# MIDI_Roundabout_revA.net
KiCad netlist of a schematic drawn in EAGLE
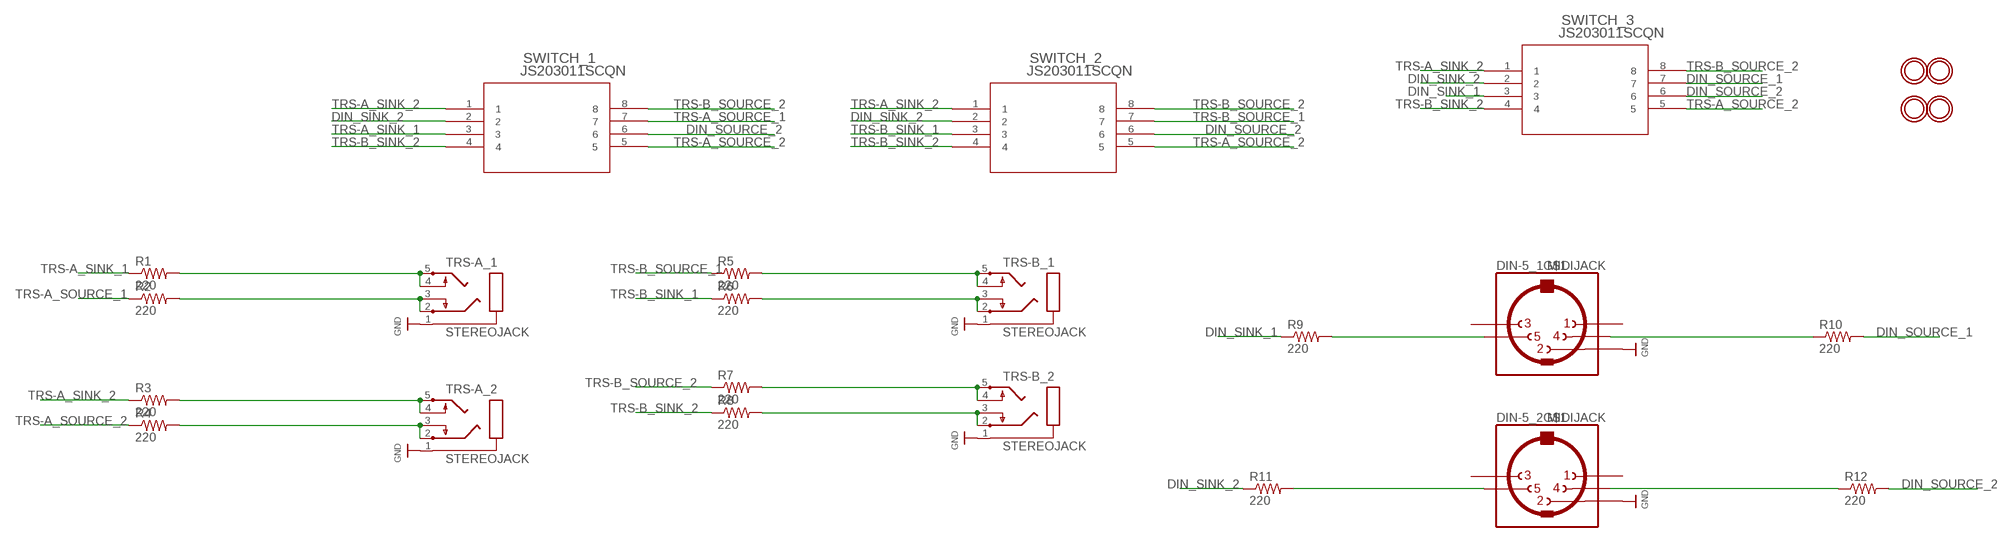
[diagram p0: schematic, sheet 1]

(export (version "E")
  (design (tool "Eeschema 10.0.6"))
  (components
    (comp (ref "DIN-5_1")
      (value "MIDIJACK")
      (footprint "eagle-import:CP-2350")
      (libsource (lib "eagle-import") (part "MIDIJACK"))
    )
    (comp (ref "DIN-5_2")
      (value "MIDIJACK")
      (footprint "eagle-import:CP-2350")
      (libsource (lib "eagle-import") (part "MIDIJACK"))
    )
    (comp (ref "R1")
      (value "220")
      (footprint "eagle-import:R0805")
      (libsource (lib "eagle-import") (part "R-US_R0805"))
    )
    (comp (ref "R2")
      (value "220")
      (footprint "eagle-import:R0805")
      (libsource (lib "eagle-import") (part "R-US_R0805"))
    )
    (comp (ref "R3")
      (value "220")
      (footprint "eagle-import:R0805")
      (libsource (lib "eagle-import") (part "R-US_R0805"))
    )
    (comp (ref "R4")
      (value "220")
      (footprint "eagle-import:R0805")
      (libsource (lib "eagle-import") (part "R-US_R0805"))
    )
    (comp (ref "R5")
      (value "220")
      (footprint "eagle-import:R0805")
      (libsource (lib "eagle-import") (part "R-US_R0805"))
    )
    (comp (ref "R6")
      (value "220")
      (footprint "eagle-import:R0805")
      (libsource (lib "eagle-import") (part "R-US_R0805"))
    )
    (comp (ref "R7")
      (value "220")
      (footprint "eagle-import:R0805")
      (libsource (lib "eagle-import") (part "R-US_R0805"))
    )
    (comp (ref "R8")
      (value "220")
      (footprint "eagle-import:R0805")
      (libsource (lib "eagle-import") (part "R-US_R0805"))
    )
    (comp (ref "R9")
      (value "220")
      (footprint "eagle-import:R0805")
      (libsource (lib "eagle-import") (part "R-US_R0805"))
    )
    (comp (ref "R10")
      (value "220")
      (footprint "eagle-import:R0805")
      (libsource (lib "eagle-import") (part "R-US_R0805"))
    )
    (comp (ref "R11")
      (value "220")
      (footprint "eagle-import:R0805")
      (libsource (lib "eagle-import") (part "R-US_R0805"))
    )
    (comp (ref "R12")
      (value "220")
      (footprint "eagle-import:R0805")
      (libsource (lib "eagle-import") (part "R-US_R0805"))
    )
    (comp (ref "SWITCH_1")
      (value "JS203011SCQN")
      (footprint "eagle-import:SWITCH_3011SCQN")
      (fields (field (name "COPYRIGHT") "Copyright (C) 2025 Ultra Librarian. All rights reserved."))
      (libsource (lib "eagle-import") (part "JS203011SCQN"))
    )
    (comp (ref "SWITCH_2")
      (value "JS203011SCQN")
      (footprint "eagle-import:SWITCH_3011SCQN")
      (fields (field (name "COPYRIGHT") "Copyright (C) 2025 Ultra Librarian. All rights reserved."))
      (libsource (lib "eagle-import") (part "JS203011SCQN"))
    )
    (comp (ref "SWITCH_3")
      (value "JS203011SCQN")
      (footprint "eagle-import:SWITCH_3011SCQN")
      (fields (field (name "COPYRIGHT") "Copyright (C) 2025 Ultra Librarian. All rights reserved."))
      (libsource (lib "eagle-import") (part "JS203011SCQN"))
    )
    (comp (ref "TRS-A_1")
      (value "STEREOJACK")
      (footprint "eagle-import:STX3100")
      (libsource (lib "eagle-import") (part "STEREOJACK"))
    )
    (comp (ref "TRS-A_2")
      (value "STEREOJACK")
      (footprint "eagle-import:STX3100")
      (libsource (lib "eagle-import") (part "STEREOJACK"))
    )
    (comp (ref "TRS-B_1")
      (value "STEREOJACK")
      (footprint "eagle-import:STX3100")
      (libsource (lib "eagle-import") (part "STEREOJACK"))
    )
    (comp (ref "TRS-B_2")
      (value "STEREOJACK")
      (footprint "eagle-import:STX3100")
      (libsource (lib "eagle-import") (part "STEREOJACK"))
    )
    (comp (ref "U$7")
      (value "MOUNTINGHOLE2.5_THICK")
      (footprint "eagle-import:MOUNTINGHOLE_2.5_PLATED_THICK")
      (libsource (lib "eagle-import") (part "MOUNTINGHOLE2.5_THICK"))
    )
    (comp (ref "U$8")
      (value "MOUNTINGHOLE2.5_THICK")
      (footprint "eagle-import:MOUNTINGHOLE_2.5_PLATED_THICK")
      (libsource (lib "eagle-import") (part "MOUNTINGHOLE2.5_THICK"))
    )
    (comp (ref "U$9")
      (value "MOUNTINGHOLE2.5_THICK")
      (footprint "eagle-import:MOUNTINGHOLE_2.5_PLATED_THICK")
      (libsource (lib "eagle-import") (part "MOUNTINGHOLE2.5_THICK"))
    )
    (comp (ref "U$10")
      (value "MOUNTINGHOLE2.5_THICK")
      (footprint "eagle-import:MOUNTINGHOLE_2.5_PLATED_THICK")
      (libsource (lib "eagle-import") (part "MOUNTINGHOLE2.5_THICK"))
    )
  )
  (nets
    (net (code "1") (name "/DIN_SINK_1") (class "Default")
      (node (ref "R9") (pin "1") (pinfunction "1_1") (pintype "passive"))
      (node (ref "SWITCH_3") (pin "3") (pinfunction "3_3") (pintype "passive"))
    )
    (net (code "2") (name "/DIN_SINK_2") (class "Default")
      (node (ref "R11") (pin "1") (pinfunction "1_1") (pintype "passive"))
      (node (ref "SWITCH_1") (pin "2") (pinfunction "2_2") (pintype "passive"))
      (node (ref "SWITCH_2") (pin "2") (pinfunction "2_2") (pintype "passive"))
      (node (ref "SWITCH_3") (pin "2") (pinfunction "2_2") (pintype "passive"))
    )
    (net (code "3") (name "/DIN_SOURCE_1") (class "Default")
      (node (ref "R10") (pin "2") (pinfunction "2_2") (pintype "passive"))
      (node (ref "SWITCH_3") (pin "7") (pinfunction "7_7") (pintype "passive"))
    )
    (net (code "4") (name "/DIN_SOURCE_2") (class "Default")
      (node (ref "R12") (pin "2") (pinfunction "2_2") (pintype "passive"))
      (node (ref "SWITCH_1") (pin "6") (pinfunction "6_6") (pintype "passive"))
      (node (ref "SWITCH_2") (pin "6") (pinfunction "6_6") (pintype "passive"))
      (node (ref "SWITCH_3") (pin "6") (pinfunction "6_6") (pintype "passive"))
    )
    (net (code "5") (name "/TRS-A_SINK_1") (class "Default")
      (node (ref "R1") (pin "1") (pinfunction "1_1") (pintype "passive"))
      (node (ref "SWITCH_1") (pin "3") (pinfunction "3_3") (pintype "passive"))
    )
    (net (code "6") (name "/TRS-A_SINK_2") (class "Default")
      (node (ref "R3") (pin "1") (pinfunction "1_1") (pintype "passive"))
      (node (ref "SWITCH_1") (pin "1") (pinfunction "1_1") (pintype "passive"))
      (node (ref "SWITCH_2") (pin "1") (pinfunction "1_1") (pintype "passive"))
      (node (ref "SWITCH_3") (pin "1") (pinfunction "1_1") (pintype "passive"))
    )
    (net (code "7") (name "/TRS-A_SOURCE_1") (class "Default")
      (node (ref "R2") (pin "1") (pinfunction "1_1") (pintype "passive"))
      (node (ref "SWITCH_1") (pin "7") (pinfunction "7_7") (pintype "passive"))
    )
    (net (code "8") (name "/TRS-A_SOURCE_2") (class "Default")
      (node (ref "R4") (pin "1") (pinfunction "1_1") (pintype "passive"))
      (node (ref "SWITCH_1") (pin "5") (pinfunction "5_5") (pintype "passive"))
      (node (ref "SWITCH_2") (pin "5") (pinfunction "5_5") (pintype "passive"))
      (node (ref "SWITCH_3") (pin "5") (pinfunction "5_5") (pintype "passive"))
    )
    (net (code "9") (name "/TRS-B_SINK_1") (class "Default")
      (node (ref "R6") (pin "1") (pinfunction "1_1") (pintype "passive"))
      (node (ref "SWITCH_2") (pin "3") (pinfunction "3_3") (pintype "passive"))
    )
    (net (code "10") (name "/TRS-B_SINK_2") (class "Default")
      (node (ref "R8") (pin "1") (pinfunction "1_1") (pintype "passive"))
      (node (ref "SWITCH_1") (pin "4") (pinfunction "4_4") (pintype "passive"))
      (node (ref "SWITCH_2") (pin "4") (pinfunction "4_4") (pintype "passive"))
      (node (ref "SWITCH_3") (pin "4") (pinfunction "4_4") (pintype "passive"))
    )
    (net (code "11") (name "/TRS-B_SOURCE_1") (class "Default")
      (node (ref "R5") (pin "1") (pinfunction "1_1") (pintype "passive"))
      (node (ref "SWITCH_2") (pin "7") (pinfunction "7_7") (pintype "passive"))
    )
    (net (code "12") (name "/TRS-B_SOURCE_2") (class "Default")
      (node (ref "R7") (pin "1") (pinfunction "1_1") (pintype "passive"))
      (node (ref "SWITCH_1") (pin "8") (pinfunction "8_8") (pintype "passive"))
      (node (ref "SWITCH_2") (pin "8") (pinfunction "8_8") (pintype "passive"))
      (node (ref "SWITCH_3") (pin "8") (pinfunction "8_8") (pintype "passive"))
    )
    (net (code "13") (name "GND") (class "Default")
      (node (ref "DIN-5_1") (pin "2") (pinfunction "2_2") (pintype "passive"))
      (node (ref "DIN-5_2") (pin "2") (pinfunction "2_2") (pintype "passive"))
      (node (ref "TRS-A_1") (pin "1") (pinfunction "1_1") (pintype "passive"))
      (node (ref "TRS-A_2") (pin "1") (pinfunction "1_1") (pintype "passive"))
      (node (ref "TRS-B_1") (pin "1") (pinfunction "1_1") (pintype "passive"))
      (node (ref "TRS-B_2") (pin "1") (pinfunction "1_1") (pintype "passive"))
    )
    (net (code "14") (name "Net-(DIN-5_1-Pad4)") (class "Default")
      (node (ref "DIN-5_1") (pin "4") (pinfunction "4_4") (pintype "passive"))
      (node (ref "R10") (pin "1") (pinfunction "1_1") (pintype "passive"))
    )
    (net (code "15") (name "Net-(DIN-5_1-Pad5)") (class "Default")
      (node (ref "DIN-5_1") (pin "5") (pinfunction "5_5") (pintype "passive"))
      (node (ref "R9") (pin "2") (pinfunction "2_2") (pintype "passive"))
    )
    (net (code "16") (name "Net-(DIN-5_2-Pad4)") (class "Default")
      (node (ref "DIN-5_2") (pin "4") (pinfunction "4_4") (pintype "passive"))
      (node (ref "R12") (pin "1") (pinfunction "1_1") (pintype "passive"))
    )
    (net (code "17") (name "Net-(DIN-5_2-Pad5)") (class "Default")
      (node (ref "DIN-5_2") (pin "5") (pinfunction "5_5") (pintype "passive"))
      (node (ref "R11") (pin "2") (pinfunction "2_2") (pintype "passive"))
    )
    (net (code "18") (name "Net-(R1-Pad2)") (class "Default")
      (node (ref "R1") (pin "2") (pinfunction "2_2") (pintype "passive"))
      (node (ref "TRS-A_1") (pin "4") (pinfunction "4_4") (pintype "passive"))
      (node (ref "TRS-A_1") (pin "5") (pinfunction "5_5") (pintype "passive"))
    )
    (net (code "19") (name "Net-(R2-Pad2)") (class "Default")
      (node (ref "R2") (pin "2") (pinfunction "2_2") (pintype "passive"))
      (node (ref "TRS-A_1") (pin "2") (pinfunction "2_2") (pintype "passive"))
      (node (ref "TRS-A_1") (pin "3") (pinfunction "3_3") (pintype "passive"))
    )
    (net (code "20") (name "Net-(R3-Pad2)") (class "Default")
      (node (ref "R3") (pin "2") (pinfunction "2_2") (pintype "passive"))
      (node (ref "TRS-A_2") (pin "4") (pinfunction "4_4") (pintype "passive"))
      (node (ref "TRS-A_2") (pin "5") (pinfunction "5_5") (pintype "passive"))
    )
    (net (code "21") (name "Net-(R4-Pad2)") (class "Default")
      (node (ref "R4") (pin "2") (pinfunction "2_2") (pintype "passive"))
      (node (ref "TRS-A_2") (pin "2") (pinfunction "2_2") (pintype "passive"))
      (node (ref "TRS-A_2") (pin "3") (pinfunction "3_3") (pintype "passive"))
    )
    (net (code "22") (name "Net-(R5-Pad2)") (class "Default")
      (node (ref "R5") (pin "2") (pinfunction "2_2") (pintype "passive"))
      (node (ref "TRS-B_1") (pin "4") (pinfunction "4_4") (pintype "passive"))
      (node (ref "TRS-B_1") (pin "5") (pinfunction "5_5") (pintype "passive"))
    )
    (net (code "23") (name "Net-(R6-Pad2)") (class "Default")
      (node (ref "R6") (pin "2") (pinfunction "2_2") (pintype "passive"))
      (node (ref "TRS-B_1") (pin "2") (pinfunction "2_2") (pintype "passive"))
      (node (ref "TRS-B_1") (pin "3") (pinfunction "3_3") (pintype "passive"))
    )
    (net (code "24") (name "Net-(R7-Pad2)") (class "Default")
      (node (ref "R7") (pin "2") (pinfunction "2_2") (pintype "passive"))
      (node (ref "TRS-B_2") (pin "4") (pinfunction "4_4") (pintype "passive"))
      (node (ref "TRS-B_2") (pin "5") (pinfunction "5_5") (pintype "passive"))
    )
    (net (code "25") (name "Net-(R8-Pad2)") (class "Default")
      (node (ref "R8") (pin "2") (pinfunction "2_2") (pintype "passive"))
      (node (ref "TRS-B_2") (pin "2") (pinfunction "2_2") (pintype "passive"))
      (node (ref "TRS-B_2") (pin "3") (pinfunction "3_3") (pintype "passive"))
    )
    (net (code "26") (name "unconnected-(DIN-5_1-Pad1)") (class "Default")
      (node (ref "DIN-5_1") (pin "1") (pinfunction "1_1") (pintype "passive"))
    )
    (net (code "27") (name "unconnected-(DIN-5_1-Pad3)") (class "Default")
      (node (ref "DIN-5_1") (pin "3") (pinfunction "3_3") (pintype "passive"))
    )
    (net (code "28") (name "unconnected-(DIN-5_2-Pad1)") (class "Default")
      (node (ref "DIN-5_2") (pin "1") (pinfunction "1_1") (pintype "passive"))
    )
    (net (code "29") (name "unconnected-(DIN-5_2-Pad3)") (class "Default")
      (node (ref "DIN-5_2") (pin "3") (pinfunction "3_3") (pintype "passive"))
    )
  )
)
